# Cahyo.net
KiCad netlist of a schematic drawn in EAGLE
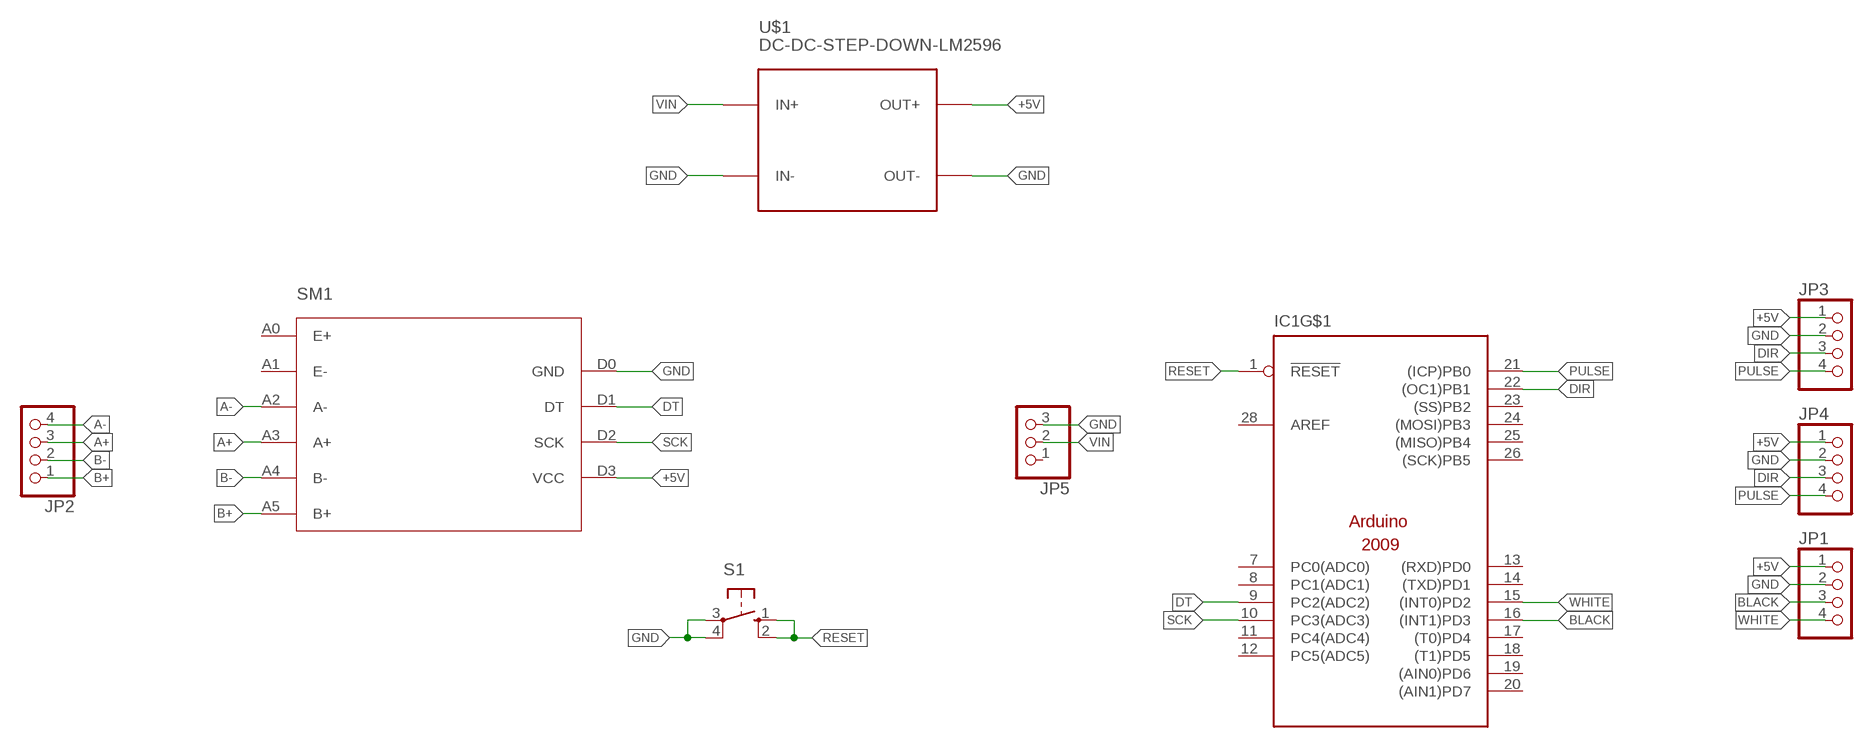
[diagram p0: schematic, sheet 1]

(export (version "E")
  (design (tool "Eeschema 10.0.6"))
  (components
    (comp (ref "IC1")
      (value "ARDUINO2009_PIN_22")
      (footprint "eagle-import:ARDUINO2009_2")
      (libsource (lib "eagle-import") (part "ARDUINO2009_PIN_22"))
    )
    (comp (ref "JP1")
      (value "PINHD-1X4")
      (footprint "eagle-import:1X04")
      (libsource (lib "eagle-import") (part "PINHD-1X4"))
    )
    (comp (ref "JP2")
      (value "PINHD-1X4")
      (footprint "eagle-import:1X04")
      (libsource (lib "eagle-import") (part "PINHD-1X4"))
    )
    (comp (ref "JP3")
      (value "PINHD-1X4")
      (footprint "eagle-import:1X04")
      (libsource (lib "eagle-import") (part "PINHD-1X4"))
    )
    (comp (ref "JP4")
      (value "PINHD-1X4")
      (footprint "eagle-import:1X04")
      (libsource (lib "eagle-import") (part "PINHD-1X4"))
    )
    (comp (ref "JP5")
      (value "PINHD-1X3")
      (footprint "eagle-import:1X03")
      (libsource (lib "eagle-import") (part "PINHD-1X3"))
    )
    (comp (ref "S1")
      (value "10-XX")
      (footprint "eagle-import:B3F-10XX")
      (fields (field (name "MPN") "B3F-1000"))
      (libsource (lib "eagle-import") (part "10-XX"))
    )
    (comp (ref "SM1")
      (value "HX711")
      (footprint "eagle-import:HX711")
      (libsource (lib "eagle-import") (part "HX711"))
    )
    (comp (ref "U$1")
      (value "DC-DC-STEP-DOWN-LM2596")
      (footprint "eagle-import:DC-DC-STEP-DOWN-LM2596")
      (libsource (lib "eagle-import") (part "DC-DC-STEP-DOWN-LM2596"))
    )
  )
  (nets
    (net (code "1") (name "+5V") (class "Default")
      (node (ref "JP1") (pin "1") (pinfunction "1_1") (pintype "passive"))
      (node (ref "JP3") (pin "1") (pinfunction "1_1") (pintype "passive"))
      (node (ref "JP4") (pin "1") (pinfunction "1_1") (pintype "passive"))
      (node (ref "SM1") (pin "D3") (pinfunction "VCC_D3") (pintype "bidirectional"))
      (node (ref "U$1") (pin "OUT+") (pinfunction "OUT+_OUT+") (pintype "bidirectional"))
    )
    (net (code "2") (name "A+") (class "Default")
      (node (ref "JP2") (pin "3") (pinfunction "3_3") (pintype "passive"))
      (node (ref "SM1") (pin "A3") (pinfunction "A+_A3") (pintype "bidirectional"))
    )
    (net (code "3") (name "A-") (class "Default")
      (node (ref "JP2") (pin "4") (pinfunction "4_4") (pintype "passive"))
      (node (ref "SM1") (pin "A2") (pinfunction "A-_A2") (pintype "bidirectional"))
    )
    (net (code "4") (name "B+") (class "Default")
      (node (ref "JP2") (pin "1") (pinfunction "1_1") (pintype "passive"))
      (node (ref "SM1") (pin "A5") (pinfunction "B+_A5") (pintype "bidirectional"))
    )
    (net (code "5") (name "B-") (class "Default")
      (node (ref "JP2") (pin "2") (pinfunction "2_2") (pintype "passive"))
      (node (ref "SM1") (pin "A4") (pinfunction "B-_A4") (pintype "bidirectional"))
    )
    (net (code "6") (name "BLACK") (class "Default")
      (node (ref "IC1") (pin "16") (pinfunction "(INT1)PD3_16") (pintype "bidirectional"))
      (node (ref "JP1") (pin "3") (pinfunction "3_3") (pintype "passive"))
    )
    (net (code "7") (name "DIR") (class "Default")
      (node (ref "IC1") (pin "22") (pinfunction "(OC1)PB1_22") (pintype "bidirectional"))
      (node (ref "JP3") (pin "3") (pinfunction "3_3") (pintype "passive"))
      (node (ref "JP4") (pin "3") (pinfunction "3_3") (pintype "passive"))
    )
    (net (code "8") (name "DT") (class "Default")
      (node (ref "IC1") (pin "9") (pinfunction "PC2(ADC2)_9") (pintype "bidirectional"))
      (node (ref "SM1") (pin "D1") (pinfunction "DT_D1") (pintype "bidirectional"))
    )
    (net (code "9") (name "GND") (class "Default")
      (node (ref "JP1") (pin "2") (pinfunction "2_2") (pintype "passive"))
      (node (ref "JP3") (pin "2") (pinfunction "2_2") (pintype "passive"))
      (node (ref "JP4") (pin "2") (pinfunction "2_2") (pintype "passive"))
      (node (ref "JP5") (pin "3") (pinfunction "3_3") (pintype "passive"))
      (node (ref "S1") (pin "3") (pinfunction "P_3") (pintype "passive"))
      (node (ref "S1") (pin "4") (pinfunction "P1_4") (pintype "passive"))
      (node (ref "SM1") (pin "D0") (pinfunction "GND_D0") (pintype "bidirectional"))
      (node (ref "U$1") (pin "IN-") (pinfunction "IN-_IN-") (pintype "bidirectional"))
      (node (ref "U$1") (pin "OUT-") (pinfunction "OUT-_OUT-") (pintype "bidirectional"))
    )
    (net (code "10") (name "PULSE") (class "Default")
      (node (ref "IC1") (pin "21") (pinfunction "(ICP)PB0_21") (pintype "bidirectional"))
      (node (ref "JP3") (pin "4") (pinfunction "4_4") (pintype "passive"))
      (node (ref "JP4") (pin "4") (pinfunction "4_4") (pintype "passive"))
    )
    (net (code "11") (name "RESET") (class "Default")
      (node (ref "IC1") (pin "1") (pinfunction "~{RESET}_1") (pintype "bidirectional"))
      (node (ref "S1") (pin "1") (pinfunction "S_1") (pintype "passive"))
      (node (ref "S1") (pin "2") (pinfunction "S1_2") (pintype "passive"))
    )
    (net (code "12") (name "SCK") (class "Default")
      (node (ref "IC1") (pin "10") (pinfunction "PC3(ADC3)_10") (pintype "bidirectional"))
      (node (ref "SM1") (pin "D2") (pinfunction "SCK_D2") (pintype "bidirectional"))
    )
    (net (code "13") (name "VIN") (class "Default")
      (node (ref "JP5") (pin "2") (pinfunction "2_2") (pintype "passive"))
      (node (ref "U$1") (pin "IN+") (pinfunction "IN+_IN+") (pintype "bidirectional"))
    )
    (net (code "14") (name "WHITE") (class "Default")
      (node (ref "IC1") (pin "15") (pinfunction "(INT0)PD2_15") (pintype "bidirectional"))
      (node (ref "JP1") (pin "4") (pinfunction "4_4") (pintype "passive"))
    )
    (net (code "15") (name "unconnected-(IC1A-(AIN0)PD6-Pad19)") (class "Default")
      (node (ref "IC1") (pin "19") (pinfunction "(AIN0)PD6_19") (pintype "bidirectional"))
    )
    (net (code "16") (name "unconnected-(IC1A-(AIN1)PD7-Pad20)") (class "Default")
      (node (ref "IC1") (pin "20") (pinfunction "(AIN1)PD7_20") (pintype "bidirectional"))
    )
    (net (code "17") (name "unconnected-(IC1A-(MISO)PB4-Pad25)") (class "Default")
      (node (ref "IC1") (pin "25") (pinfunction "(MISO)PB4_25") (pintype "bidirectional"))
    )
    (net (code "18") (name "unconnected-(IC1A-(MOSI)PB3-Pad24)") (class "Default")
      (node (ref "IC1") (pin "24") (pinfunction "(MOSI)PB3_24") (pintype "bidirectional"))
    )
    (net (code "19") (name "unconnected-(IC1A-(RXD)PD0-Pad13)") (class "Default")
      (node (ref "IC1") (pin "13") (pinfunction "(RXD)PD0_13") (pintype "bidirectional"))
    )
    (net (code "20") (name "unconnected-(IC1A-(SCK)PB5-Pad26)") (class "Default")
      (node (ref "IC1") (pin "26") (pinfunction "(SCK)PB5_26") (pintype "bidirectional"))
    )
    (net (code "21") (name "unconnected-(IC1A-(SS)PB2-Pad23)") (class "Default")
      (node (ref "IC1") (pin "23") (pinfunction "(SS)PB2_23") (pintype "bidirectional"))
    )
    (net (code "22") (name "unconnected-(IC1A-(T0)PD4-Pad17)") (class "Default")
      (node (ref "IC1") (pin "17") (pinfunction "(T0)PD4_17") (pintype "bidirectional"))
    )
    (net (code "23") (name "unconnected-(IC1A-(T1)PD5-Pad18)") (class "Default")
      (node (ref "IC1") (pin "18") (pinfunction "(T1)PD5_18") (pintype "bidirectional"))
    )
    (net (code "24") (name "unconnected-(IC1A-(TXD)PD1-Pad14)") (class "Default")
      (node (ref "IC1") (pin "14") (pinfunction "(TXD)PD1_14") (pintype "bidirectional"))
    )
    (net (code "25") (name "unconnected-(IC1A-AREF-Pad28)") (class "Default")
      (node (ref "IC1") (pin "28") (pinfunction "AREF_28") (pintype "bidirectional"))
    )
    (net (code "26") (name "unconnected-(IC1A-PC0(ADC0)-Pad7)") (class "Default")
      (node (ref "IC1") (pin "7") (pinfunction "PC0(ADC0)_7") (pintype "bidirectional"))
    )
    (net (code "27") (name "unconnected-(IC1A-PC1(ADC1)-Pad8)") (class "Default")
      (node (ref "IC1") (pin "8") (pinfunction "PC1(ADC1)_8") (pintype "bidirectional"))
    )
    (net (code "28") (name "unconnected-(IC1A-PC4(ADC4)-Pad11)") (class "Default")
      (node (ref "IC1") (pin "11") (pinfunction "PC4(ADC4)_11") (pintype "bidirectional"))
    )
    (net (code "29") (name "unconnected-(IC1A-PC5(ADC5)-Pad12)") (class "Default")
      (node (ref "IC1") (pin "12") (pinfunction "PC5(ADC5)_12") (pintype "bidirectional"))
    )
    (net (code "30") (name "unconnected-(JP5-Pad1)") (class "Default")
      (node (ref "JP5") (pin "1") (pinfunction "1_1") (pintype "passive"))
    )
    (net (code "31") (name "unconnected-(SM1-E+-PadA0)") (class "Default")
      (node (ref "SM1") (pin "A0") (pinfunction "E+_A0") (pintype "bidirectional"))
    )
    (net (code "32") (name "unconnected-(SM1-E--PadA1)") (class "Default")
      (node (ref "SM1") (pin "A1") (pinfunction "E-_A1") (pintype "bidirectional"))
    )
  )
)
